# v2.net
KiCad netlist of a schematic drawn in EAGLE
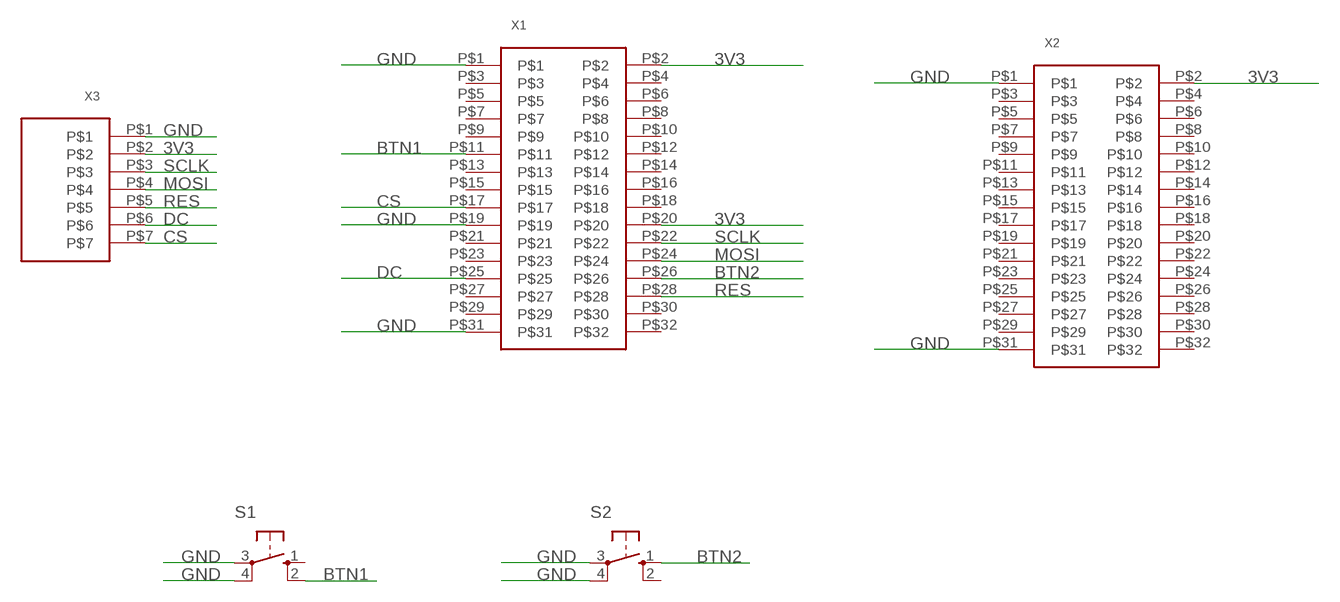
[diagram p0: schematic, sheet 1]

(export (version "E")
  (design (tool "Eeschema 10.0.6"))
  (components
    (comp (ref "S1")
      (value "S1")
      (footprint "eagle-import:B3F-40XX")
      (fields (field (name "MF") "OMRON COMPONENTS USA") (field (name "MPN") "B3F-4000"))
      (libsource (lib "eagle-import") (part "40-XX"))
    )
    (comp (ref "S2")
      (value "S2")
      (footprint "eagle-import:B3F-40XX")
      (fields (field (name "MF") "OMRON COMPONENTS USA") (field (name "MPN") "B3F-4000"))
      (libsource (lib "eagle-import") (part "40-XX"))
    )
    (comp (ref "X1")
      (value "2X16-SOCKET-HEADER")
      (footprint "eagle-import:2X16-SOCKET-HEADER")
      (libsource (lib "eagle-import") (part "2X16-SOCKET-HEADER"))
    )
    (comp (ref "X2")
      (value "2X16-SOCKET-HEADER")
      (footprint "eagle-import:2X16-SOCKET-HEADER")
      (libsource (lib "eagle-import") (part "2X16-SOCKET-HEADER"))
    )
    (comp (ref "X3")
      (value "1X7-SOCKET-HEADER")
      (footprint "eagle-import:1X7-SOCKET-HEADER")
      (libsource (lib "eagle-import") (part "1X7-SOCKET-HEADER"))
    )
  )
  (nets
    (net (code "1") (name "/3V3") (class "Default")
      (node (ref "X1") (pin "P$2") (pinfunction "P$2_P$2") (pintype "passive"))
      (node (ref "X1") (pin "P$20") (pinfunction "P$20_P$20") (pintype "passive"))
      (node (ref "X2") (pin "P$2") (pinfunction "P$2_P$2") (pintype "passive"))
      (node (ref "X3") (pin "P$2") (pinfunction "P$2_P$2") (pintype "passive"))
    )
    (net (code "2") (name "/BTN1") (class "Default")
      (node (ref "S1") (pin "2") (pinfunction "S1_2") (pintype "passive"))
      (node (ref "X1") (pin "P$11") (pinfunction "P$11_P$11") (pintype "passive"))
    )
    (net (code "3") (name "/BTN2") (class "Default")
      (node (ref "S2") (pin "1") (pinfunction "S_1") (pintype "passive"))
      (node (ref "X1") (pin "P$26") (pinfunction "P$26_P$26") (pintype "passive"))
    )
    (net (code "4") (name "/CS") (class "Default")
      (node (ref "X1") (pin "P$17") (pinfunction "P$17_P$17") (pintype "passive"))
      (node (ref "X3") (pin "P$7") (pinfunction "P$7_P$7") (pintype "passive"))
    )
    (net (code "5") (name "/DC") (class "Default")
      (node (ref "X1") (pin "P$25") (pinfunction "P$25_P$25") (pintype "passive"))
      (node (ref "X3") (pin "P$6") (pinfunction "P$6_P$6") (pintype "passive"))
    )
    (net (code "6") (name "/GND") (class "Default")
      (node (ref "S1") (pin "3") (pinfunction "P_3") (pintype "passive"))
      (node (ref "S1") (pin "4") (pinfunction "P1_4") (pintype "passive"))
      (node (ref "S2") (pin "3") (pinfunction "P_3") (pintype "passive"))
      (node (ref "S2") (pin "4") (pinfunction "P1_4") (pintype "passive"))
      (node (ref "X1") (pin "P$1") (pinfunction "P$1_P$1") (pintype "passive"))
      (node (ref "X1") (pin "P$19") (pinfunction "P$19_P$19") (pintype "passive"))
      (node (ref "X1") (pin "P$31") (pinfunction "P$31_P$31") (pintype "passive"))
      (node (ref "X2") (pin "P$1") (pinfunction "P$1_P$1") (pintype "passive"))
      (node (ref "X2") (pin "P$31") (pinfunction "P$31_P$31") (pintype "passive"))
      (node (ref "X3") (pin "P$1") (pinfunction "P$1_P$1") (pintype "passive"))
    )
    (net (code "7") (name "/MOSI") (class "Default")
      (node (ref "X1") (pin "P$24") (pinfunction "P$24_P$24") (pintype "passive"))
      (node (ref "X3") (pin "P$4") (pinfunction "P$4_P$4") (pintype "passive"))
    )
    (net (code "8") (name "/RES") (class "Default")
      (node (ref "X1") (pin "P$28") (pinfunction "P$28_P$28") (pintype "passive"))
      (node (ref "X3") (pin "P$5") (pinfunction "P$5_P$5") (pintype "passive"))
    )
    (net (code "9") (name "/SCLK") (class "Default")
      (node (ref "X1") (pin "P$22") (pinfunction "P$22_P$22") (pintype "passive"))
      (node (ref "X3") (pin "P$3") (pinfunction "P$3_P$3") (pintype "passive"))
    )
    (net (code "10") (name "unconnected-(S1-S-Pad1)") (class "Default")
      (node (ref "S1") (pin "1") (pinfunction "S_1") (pintype "passive"))
    )
    (net (code "11") (name "unconnected-(S2-S1-Pad2)") (class "Default")
      (node (ref "S2") (pin "2") (pinfunction "S1_2") (pintype "passive"))
    )
    (net (code "12") (name "unconnected-(X1-PadP$3)") (class "Default")
      (node (ref "X1") (pin "P$3") (pinfunction "P$3_P$3") (pintype "passive"))
    )
    (net (code "13") (name "unconnected-(X1-PadP$4)") (class "Default")
      (node (ref "X1") (pin "P$4") (pinfunction "P$4_P$4") (pintype "passive"))
    )
    (net (code "14") (name "unconnected-(X1-PadP$5)") (class "Default")
      (node (ref "X1") (pin "P$5") (pinfunction "P$5_P$5") (pintype "passive"))
    )
    (net (code "15") (name "unconnected-(X1-PadP$6)") (class "Default")
      (node (ref "X1") (pin "P$6") (pinfunction "P$6_P$6") (pintype "passive"))
    )
    (net (code "16") (name "unconnected-(X1-PadP$7)") (class "Default")
      (node (ref "X1") (pin "P$7") (pinfunction "P$7_P$7") (pintype "passive"))
    )
    (net (code "17") (name "unconnected-(X1-PadP$8)") (class "Default")
      (node (ref "X1") (pin "P$8") (pinfunction "P$8_P$8") (pintype "passive"))
    )
    (net (code "18") (name "unconnected-(X1-PadP$9)") (class "Default")
      (node (ref "X1") (pin "P$9") (pinfunction "P$9_P$9") (pintype "passive"))
    )
    (net (code "19") (name "unconnected-(X1-PadP$10)") (class "Default")
      (node (ref "X1") (pin "P$10") (pinfunction "P$10_P$10") (pintype "passive"))
    )
    (net (code "20") (name "unconnected-(X1-PadP$12)") (class "Default")
      (node (ref "X1") (pin "P$12") (pinfunction "P$12_P$12") (pintype "passive"))
    )
    (net (code "21") (name "unconnected-(X1-PadP$13)") (class "Default")
      (node (ref "X1") (pin "P$13") (pinfunction "P$13_P$13") (pintype "passive"))
    )
    (net (code "22") (name "unconnected-(X1-PadP$14)") (class "Default")
      (node (ref "X1") (pin "P$14") (pinfunction "P$14_P$14") (pintype "passive"))
    )
    (net (code "23") (name "unconnected-(X1-PadP$15)") (class "Default")
      (node (ref "X1") (pin "P$15") (pinfunction "P$15_P$15") (pintype "passive"))
    )
    (net (code "24") (name "unconnected-(X1-PadP$16)") (class "Default")
      (node (ref "X1") (pin "P$16") (pinfunction "P$16_P$16") (pintype "passive"))
    )
    (net (code "25") (name "unconnected-(X1-PadP$18)") (class "Default")
      (node (ref "X1") (pin "P$18") (pinfunction "P$18_P$18") (pintype "passive"))
    )
    (net (code "26") (name "unconnected-(X1-PadP$21)") (class "Default")
      (node (ref "X1") (pin "P$21") (pinfunction "P$21_P$21") (pintype "passive"))
    )
    (net (code "27") (name "unconnected-(X1-PadP$23)") (class "Default")
      (node (ref "X1") (pin "P$23") (pinfunction "P$23_P$23") (pintype "passive"))
    )
    (net (code "28") (name "unconnected-(X1-PadP$27)") (class "Default")
      (node (ref "X1") (pin "P$27") (pinfunction "P$27_P$27") (pintype "passive"))
    )
    (net (code "29") (name "unconnected-(X1-PadP$29)") (class "Default")
      (node (ref "X1") (pin "P$29") (pinfunction "P$29_P$29") (pintype "passive"))
    )
    (net (code "30") (name "unconnected-(X1-PadP$30)") (class "Default")
      (node (ref "X1") (pin "P$30") (pinfunction "P$30_P$30") (pintype "passive"))
    )
    (net (code "31") (name "unconnected-(X1-PadP$32)") (class "Default")
      (node (ref "X1") (pin "P$32") (pinfunction "P$32_P$32") (pintype "passive"))
    )
    (net (code "32") (name "unconnected-(X2-PadP$3)") (class "Default")
      (node (ref "X2") (pin "P$3") (pinfunction "P$3_P$3") (pintype "passive"))
    )
    (net (code "33") (name "unconnected-(X2-PadP$4)") (class "Default")
      (node (ref "X2") (pin "P$4") (pinfunction "P$4_P$4") (pintype "passive"))
    )
    (net (code "34") (name "unconnected-(X2-PadP$5)") (class "Default")
      (node (ref "X2") (pin "P$5") (pinfunction "P$5_P$5") (pintype "passive"))
    )
    (net (code "35") (name "unconnected-(X2-PadP$6)") (class "Default")
      (node (ref "X2") (pin "P$6") (pinfunction "P$6_P$6") (pintype "passive"))
    )
    (net (code "36") (name "unconnected-(X2-PadP$7)") (class "Default")
      (node (ref "X2") (pin "P$7") (pinfunction "P$7_P$7") (pintype "passive"))
    )
    (net (code "37") (name "unconnected-(X2-PadP$8)") (class "Default")
      (node (ref "X2") (pin "P$8") (pinfunction "P$8_P$8") (pintype "passive"))
    )
    (net (code "38") (name "unconnected-(X2-PadP$9)") (class "Default")
      (node (ref "X2") (pin "P$9") (pinfunction "P$9_P$9") (pintype "passive"))
    )
    (net (code "39") (name "unconnected-(X2-PadP$10)") (class "Default")
      (node (ref "X2") (pin "P$10") (pinfunction "P$10_P$10") (pintype "passive"))
    )
    (net (code "40") (name "unconnected-(X2-PadP$11)") (class "Default")
      (node (ref "X2") (pin "P$11") (pinfunction "P$11_P$11") (pintype "passive"))
    )
    (net (code "41") (name "unconnected-(X2-PadP$12)") (class "Default")
      (node (ref "X2") (pin "P$12") (pinfunction "P$12_P$12") (pintype "passive"))
    )
    (net (code "42") (name "unconnected-(X2-PadP$13)") (class "Default")
      (node (ref "X2") (pin "P$13") (pinfunction "P$13_P$13") (pintype "passive"))
    )
    (net (code "43") (name "unconnected-(X2-PadP$14)") (class "Default")
      (node (ref "X2") (pin "P$14") (pinfunction "P$14_P$14") (pintype "passive"))
    )
    (net (code "44") (name "unconnected-(X2-PadP$15)") (class "Default")
      (node (ref "X2") (pin "P$15") (pinfunction "P$15_P$15") (pintype "passive"))
    )
    (net (code "45") (name "unconnected-(X2-PadP$16)") (class "Default")
      (node (ref "X2") (pin "P$16") (pinfunction "P$16_P$16") (pintype "passive"))
    )
    (net (code "46") (name "unconnected-(X2-PadP$17)") (class "Default")
      (node (ref "X2") (pin "P$17") (pinfunction "P$17_P$17") (pintype "passive"))
    )
    (net (code "47") (name "unconnected-(X2-PadP$18)") (class "Default")
      (node (ref "X2") (pin "P$18") (pinfunction "P$18_P$18") (pintype "passive"))
    )
    (net (code "48") (name "unconnected-(X2-PadP$19)") (class "Default")
      (node (ref "X2") (pin "P$19") (pinfunction "P$19_P$19") (pintype "passive"))
    )
    (net (code "49") (name "unconnected-(X2-PadP$20)") (class "Default")
      (node (ref "X2") (pin "P$20") (pinfunction "P$20_P$20") (pintype "passive"))
    )
    (net (code "50") (name "unconnected-(X2-PadP$21)") (class "Default")
      (node (ref "X2") (pin "P$21") (pinfunction "P$21_P$21") (pintype "passive"))
    )
    (net (code "51") (name "unconnected-(X2-PadP$22)") (class "Default")
      (node (ref "X2") (pin "P$22") (pinfunction "P$22_P$22") (pintype "passive"))
    )
    (net (code "52") (name "unconnected-(X2-PadP$23)") (class "Default")
      (node (ref "X2") (pin "P$23") (pinfunction "P$23_P$23") (pintype "passive"))
    )
    (net (code "53") (name "unconnected-(X2-PadP$24)") (class "Default")
      (node (ref "X2") (pin "P$24") (pinfunction "P$24_P$24") (pintype "passive"))
    )
    (net (code "54") (name "unconnected-(X2-PadP$25)") (class "Default")
      (node (ref "X2") (pin "P$25") (pinfunction "P$25_P$25") (pintype "passive"))
    )
    (net (code "55") (name "unconnected-(X2-PadP$26)") (class "Default")
      (node (ref "X2") (pin "P$26") (pinfunction "P$26_P$26") (pintype "passive"))
    )
    (net (code "56") (name "unconnected-(X2-PadP$27)") (class "Default")
      (node (ref "X2") (pin "P$27") (pinfunction "P$27_P$27") (pintype "passive"))
    )
    (net (code "57") (name "unconnected-(X2-PadP$28)") (class "Default")
      (node (ref "X2") (pin "P$28") (pinfunction "P$28_P$28") (pintype "passive"))
    )
    (net (code "58") (name "unconnected-(X2-PadP$29)") (class "Default")
      (node (ref "X2") (pin "P$29") (pinfunction "P$29_P$29") (pintype "passive"))
    )
    (net (code "59") (name "unconnected-(X2-PadP$30)") (class "Default")
      (node (ref "X2") (pin "P$30") (pinfunction "P$30_P$30") (pintype "passive"))
    )
    (net (code "60") (name "unconnected-(X2-PadP$32)") (class "Default")
      (node (ref "X2") (pin "P$32") (pinfunction "P$32_P$32") (pintype "passive"))
    )
  )
)
